# MCU.net
KiCad netlist of a schematic drawn in Altium Designer
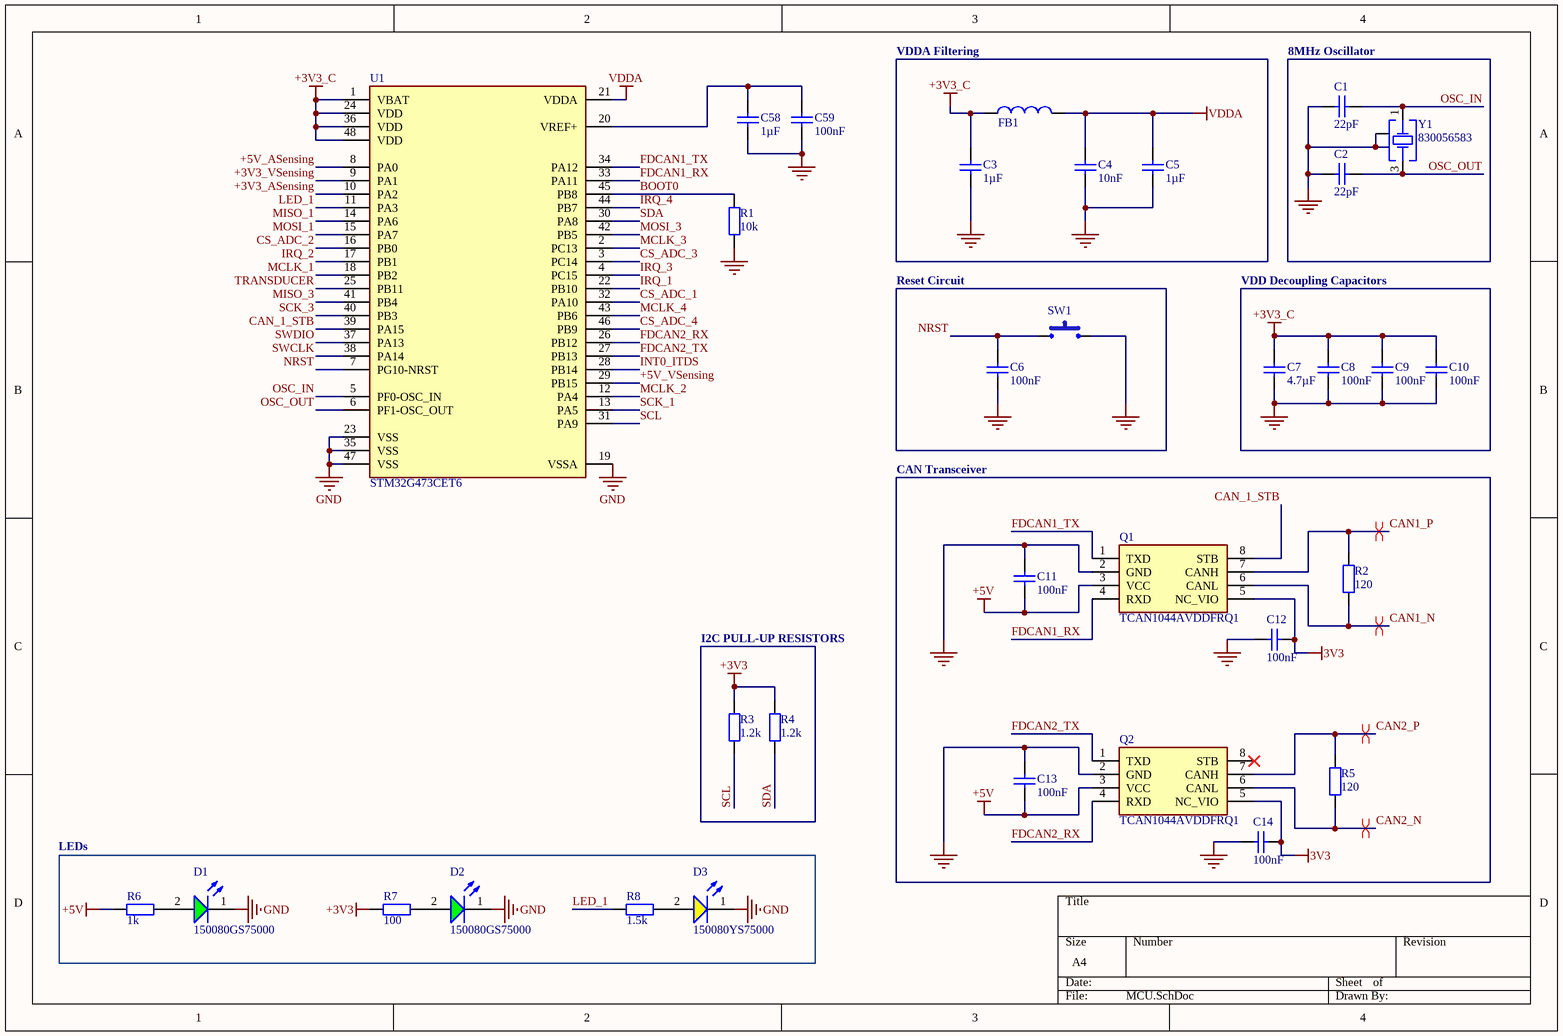
[diagram p0: MCU.SchDoc]

(export (version "E")
  (design (tool "Eeschema 10.0.6"))
  (components
    (comp (ref "C1")
      (value "22pF")
      (footprint "WCAP-CSGP_0603_L1.6W0.8H0.8_Reflow")
      (description "WCAP-CSGP Multilayer Ceramic Chip Capacitor, General Purpose, size 0603, NP0, 22pF, 25VDC")
      (fields
        (field (name "MANUFACTURER") "Wurth Elektronik")
        (field (name "MANUFACTURER PART NUMBER") "885012006034")
      )
      (libsource (lib "LEEM UPM") (part "885012209047R"))
    )
    (comp (ref "C2")
      (value "22pF")
      (footprint "WCAP-CSGP_0603_L1.6W0.8H0.8_Reflow")
      (description "WCAP-CSGP Multilayer Ceramic Chip Capacitor, General Purpose, size 0603, NP0, 22pF, 25VDC")
      (fields
        (field (name "MANUFACTURER") "Wurth Elektronik")
        (field (name "MANUFACTURER PART NUMBER") "885012006034")
      )
      (libsource (lib "LEEM UPM") (part "885012209047R"))
    )
    (comp (ref "C3")
      (value "1µF")
      (footprint "WCAP-CSGP_0603_L1.6W0.8H0.8_Reflow")
      (description "WCAP-CSGP Multilayer Ceramic Chip Capacitor, General Purpose, size 0603, X7R, 1uF, 16VDC")
      (fields
        (field (name "MANUFACTURER") "Wurth Elektronik")
        (field (name "MANUFACTURER PART NUMBER") "885012206052")
      )
      (libsource (lib "LEEM UPM") (part "885012209047R"))
    )
    (comp (ref "C4")
      (value "10nF")
      (footprint "WCAP-CSGP_0603_L1.6W0.8H0.8_Reflow")
      (description "WCAP-CSGP Multilayer Ceramic Chip Capacitor, General Purpose, size 0603, X7R, 10nF, 25VDC")
      (fields
        (field (name "MANUFACTURER") "Wurth Elektronik")
        (field (name "MANUFACTURER PART NUMBER") "885012206065")
      )
      (libsource (lib "LEEM UPM") (part "885012209047R"))
    )
    (comp (ref "C5")
      (value "1µF")
      (footprint "WCAP-CSGP_0603_L1.6W0.8H0.8_Reflow")
      (description "WCAP-CSGP Multilayer Ceramic Chip Capacitor, General Purpose, size 0603, X7R, 1uF, 16VDC")
      (fields
        (field (name "MANUFACTURER") "Wurth Elektronik")
        (field (name "MANUFACTURER PART NUMBER") "885012206052")
      )
      (libsource (lib "LEEM UPM") (part "885012209047R"))
    )
    (comp (ref "C6")
      (value "100nF")
      (footprint "WCAP-CSGP_0603_L1.6W0.8H0.8_Reflow")
      (description "WCAP-CSGP Multilayer Ceramic Chip Capacitor, General Purpose, size 0603, X7R, 100nF, 25VDC")
      (fields
        (field (name "MANUFACTURER") "Wurth Elektronik")
        (field (name "MANUFACTURER PART NUMBER") "885012206071")
      )
      (libsource (lib "LEEM UPM") (part "885012209047R"))
    )
    (comp (ref "C7")
      (value "4.7µF")
      (footprint "WCAP-CSGP_0603_L1.6W0.8H0.8_Reflow")
      (description "WCAP-CSGP Multilayer Ceramic Chip Capacitor, General Purpose, size 0603, X5R, 4.7uF, 10VDC")
      (fields
        (field (name "MANUFACTURER PART NUMBER") "885012106012")
        (field (name "MANUFACTURER") "Wurth Elektronik")
      )
      (libsource (lib "LEEM UPM") (part "885012209047R"))
    )
    (comp (ref "C8")
      (value "100nF")
      (footprint "WCAP-CSGP_0603_L1.6W0.8H0.8_Reflow")
      (description "WCAP-CSGP Multilayer Ceramic Chip Capacitor, General Purpose, size 0603, X7R, 100nF, 25VDC")
      (fields
        (field (name "MANUFACTURER") "Wurth Elektronik")
        (field (name "MANUFACTURER PART NUMBER") "885012206071")
      )
      (libsource (lib "LEEM UPM") (part "885012209047R"))
    )
    (comp (ref "C9")
      (value "100nF")
      (footprint "WCAP-CSGP_0603_L1.6W0.8H0.8_Reflow")
      (description "WCAP-CSGP Multilayer Ceramic Chip Capacitor, General Purpose, size 0603, X7R, 100nF, 25VDC")
      (fields
        (field (name "MANUFACTURER") "Wurth Elektronik")
        (field (name "MANUFACTURER PART NUMBER") "885012206071")
      )
      (libsource (lib "LEEM UPM") (part "885012209047R"))
    )
    (comp (ref "C10")
      (value "100nF")
      (footprint "WCAP-CSGP_0603_L1.6W0.8H0.8_Reflow")
      (description "WCAP-CSGP Multilayer Ceramic Chip Capacitor, General Purpose, size 0603, X7R, 100nF, 25VDC")
      (fields
        (field (name "MANUFACTURER") "Wurth Elektronik")
        (field (name "MANUFACTURER PART NUMBER") "885012206071")
      )
      (libsource (lib "LEEM UPM") (part "885012209047R"))
    )
    (comp (ref "C11")
      (value "100nF")
      (footprint "WCAP-CSGP_0603_L1.6W0.8H0.8_Reflow")
      (description "WCAP-CSGP Multilayer Ceramic Chip Capacitor, General Purpose, size 0603, X7R, 100nF, 25VDC")
      (fields
        (field (name "MANUFACTURER") "Wurth Elektronik")
        (field (name "MANUFACTURER PART NUMBER") "885012206071")
      )
      (libsource (lib "LEEM UPM") (part "885012209047R"))
    )
    (comp (ref "C12")
      (value "100nF")
      (footprint "WCAP-CSGP_0603_L1.6W0.8H0.8_Reflow")
      (description "WCAP-CSGP Multilayer Ceramic Chip Capacitor, General Purpose, size 0603, X7R, 100nF, 25VDC")
      (fields
        (field (name "MANUFACTURER") "Wurth Elektronik")
        (field (name "MANUFACTURER PART NUMBER") "885012206071")
      )
      (libsource (lib "LEEM UPM") (part "885012209047R"))
    )
    (comp (ref "C13")
      (value "100nF")
      (footprint "WCAP-CSGP_0603_L1.6W0.8H0.8_Reflow")
      (description "WCAP-CSGP Multilayer Ceramic Chip Capacitor, General Purpose, size 0603, X7R, 100nF, 25VDC")
      (fields
        (field (name "MANUFACTURER") "Wurth Elektronik")
        (field (name "MANUFACTURER PART NUMBER") "885012206071")
      )
      (libsource (lib "LEEM UPM") (part "885012209047R"))
    )
    (comp (ref "C14")
      (value "100nF")
      (footprint "WCAP-CSGP_0603_L1.6W0.8H0.8_Reflow")
      (description "WCAP-CSGP Multilayer Ceramic Chip Capacitor, General Purpose, size 0603, X7R, 100nF, 25VDC")
      (fields
        (field (name "MANUFACTURER") "Wurth Elektronik")
        (field (name "MANUFACTURER PART NUMBER") "885012206071")
      )
      (libsource (lib "LEEM UPM") (part "885012209047R"))
    )
    (comp (ref "C58")
      (value "1µF")
      (footprint "WCAP-CSGP_0603_L1.6W0.8H0.8_Reflow")
      (description "WCAP-CSGP Multilayer Ceramic Chip Capacitor, General Purpose, size 0603, X7R, 1uF, 16VDC")
      (fields
        (field (name "MANUFACTURER") "Wurth Elektronik")
        (field (name "MANUFACTURER PART NUMBER") "885012206052")
      )
      (libsource (lib "LEEM UPM") (part "885012209047R"))
    )
    (comp (ref "C59")
      (value "100nF")
      (footprint "WCAP-CSGP_0603_L1.6W0.8H0.8_Reflow")
      (description "WCAP-CSGP Multilayer Ceramic Chip Capacitor, General Purpose, size 0603, X7R, 100nF, 25VDC")
      (fields
        (field (name "MANUFACTURER") "Wurth Elektronik")
        (field (name "MANUFACTURER PART NUMBER") "885012206071")
      )
      (libsource (lib "LEEM UPM") (part "885012209047R"))
    )
    (comp (ref "D1")
      (value "150080GS75000")
      (footprint "WL-SMCW_0805_150080xx75000")
      (description "WL-SMCW Mono-color Chip LED Waterclear, SMT, size 0805, Green, 3.2V, 140°")
      (fields (field (name "MANUFACTURER") "Wurth Elektronik"))
      (libsource (lib "LEEM UPM") (part "150120VS87000"))
    )
    (comp (ref "D2")
      (value "150080GS75000")
      (footprint "WL-SMCW_0805_150080xx75000")
      (description "WL-SMCW Mono-color Chip LED Waterclear, SMT, size 0805, Green, 3.2V, 140°")
      (fields (field (name "MANUFACTURER") "Wurth Elektronik"))
      (libsource (lib "LEEM UPM") (part "150120VS87000"))
    )
    (comp (ref "D3")
      (value "150080YS75000")
      (footprint "WL-SMCW_0805_150080xx75000")
      (description "WL-SMCW Mono-color Chip LED Waterclear, SMT, size 0805, Yellow, 2V, 140°")
      (fields (field (name "MANUFACTURER") "Wurth Elektronik"))
      (libsource (lib "LEEM UPM") (part "150120YS87000"))
    )
    (comp (ref "FB1")
      (value "742792625")
      (footprint "WE-CBF_0603_L1.6W0.8H0.8_HC")
      (description "WE-CBF SMT EMI Suppression Ferrite Bead, size 0603, 120Ohm, 2A")
      (fields (field (name "MANUFACTURER") "Wurth Elektronik"))
      (libsource (lib "LEEM UPM") (part "7427928801"))
    )
    (comp (ref "Q1")
      (value "TCAN1044AVDDFRQ1")
      (footprint "FP-DDF0008A-MFG")
      (description "Enhanced automotive CAN transceiver with standby 8-SOT-23-THIN -40 to 150")
      (libsource (lib "LEEM UPM") (part "TCAN1044A"))
    )
    (comp (ref "Q2")
      (value "TCAN1044AVDDFRQ1")
      (footprint "FP-DDF0008A-MFG")
      (description "Enhanced automotive CAN transceiver with standby 8-SOT-23-THIN -40 to 150")
      (libsource (lib "LEEM UPM") (part "TCAN1044A"))
    )
    (comp (ref "R1")
      (value "10k")
      (footprint "WRIS-RSKS_0603_Reflow")
      (description "WRIS-RSKS Thick Film Resistor, size 0603, 10000Ohm, 100mW")
      (fields
        (field (name "MANUFACTURER") "Wurth Elektronik")
        (field (name "MANUFACTURER PART NUMBER") "560112116005")
      )
      (libsource (lib "LEEM UPM") (part "560112140010"))
    )
    (comp (ref "R2")
      (value "120")
      (footprint "RCS0805120RFKEA-Footprint-1")
      (fields (field (name "POWER") "500mW") (field (name "Comment") "RCS0805120RFKEA"))
      (libsource (lib "LEEM UPM") (part "RCS0805120"))
    )
    (comp (ref "R3")
      (value "1.2k")
      (footprint "WRIS-RSKS_0603_Reflow")
      (description "WRIS-RSKS Thick Film Resistor, size 0603, 1200Ohm, 100mW")
      (fields
        (field (name "MANUFACTURER PART NUMBER") "560112116070")
        (field (name "MANUFACTURER") "Wurth Elektronik")
      )
      (libsource (lib "LEEM UPM") (part "560112140010"))
    )
    (comp (ref "R4")
      (value "1.2k")
      (footprint "WRIS-RSKS_0603_Reflow")
      (description "WRIS-RSKS Thick Film Resistor, size 0603, 1200Ohm, 100mW")
      (fields
        (field (name "MANUFACTURER PART NUMBER") "560112116070")
        (field (name "MANUFACTURER") "Wurth Elektronik")
      )
      (libsource (lib "LEEM UPM") (part "560112140010"))
    )
    (comp (ref "R5")
      (value "120")
      (footprint "RCS0805120RFKEA-Footprint-1")
      (fields (field (name "POWER") "500mW") (field (name "Comment") "RCS0805120RFKEA"))
      (libsource (lib "LEEM UPM") (part "RCS0805120"))
    )
    (comp (ref "R6")
      (value "1k")
      (footprint "WRIS-RSKS_0603_Reflow")
      (description "WRIS-RSKS Thick Film Resistor, size 0603, 1000Ohm, 100mW")
      (fields
        (field (name "MANUFACTURER PART NUMBER") "560112116014")
        (field (name "MANUFACTURER") "Wurth Elektronik")
      )
      (libsource (lib "") (part "560112140010_1"))
    )
    (comp (ref "R7")
      (value "100")
      (footprint "WRIS-RSKS_0603_Reflow")
      (description "WRIS-RSKS Thick Film Resistor, size 0603, 100Ohm, 100mW")
      (fields
        (field (name "MANUFACTURER") "Wurth Elektronik")
        (field (name "MANUFACTURER PART NUMBER") "560112116009")
      )
      (libsource (lib "") (part "560112140010_1"))
    )
    (comp (ref "R8")
      (value "1.5k")
      (footprint "WRIS-RSKS_0603_Reflow")
      (description "WRIS-RSKS Thick Film Resistor, size 0603, 1500Ohm, 100mW")
      (fields
        (field (name "MANUFACTURER") "Wurth Elektronik")
        (field (name "MANUFACTURER PART NUMBER") "560112116038")
      )
      (libsource (lib "") (part "560112140010_1"))
    )
    (comp (ref "SW1")
      (value "PTS815SJM250SMTRLFS")
      (footprint "PTS815SJM250SMTRLFS-Footprint-1")
      (libsource (lib "LEEM UPM") (part "PTS815S"))
    )
    (comp (ref "U1")
      (value "STM32G473CET6")
      (footprint "STM32G0C1RET6-Footprint-1")
      (libsource (lib "LEEM UPM") (part "STM32G473xE"))
    )
    (comp (ref "Y1")
      (value "830056583")
      (footprint "WE-XTAL_CFPX-104")
      (description "WE-XTAL Quartz Crystal, SMT, CFPX-104, 10MHz, +/-30ppm")
      (fields (field (name "MANUFACTURER") "Wurth Elektronik"))
      (libsource (lib "LEEM UPM") (part "830108161901"))
    )
  )
  (nets
    (net (code "1") (name "+3V3") (class "Default")
      (node (ref "R3") (pin "2") (pinfunction "2_2") (pintype "passive"))
      (node (ref "R4") (pin "2") (pinfunction "2_2") (pintype "passive"))
      (node (ref "R7") (pin "1") (pinfunction "1_1") (pintype "passive"))
    )
    (net (code "2") (name "+3V3_C") (class "Default")
      (node (ref "C10") (pin "2") (pinfunction "2_2") (pintype "passive"))
      (node (ref "C12") (pin "1") (pinfunction "1_1") (pintype "passive"))
      (node (ref "C14") (pin "1") (pinfunction "1_1") (pintype "passive"))
      (node (ref "C3") (pin "2") (pinfunction "2_2") (pintype "passive"))
      (node (ref "C7") (pin "2") (pinfunction "2_2") (pintype "passive"))
      (node (ref "C8") (pin "2") (pinfunction "2_2") (pintype "passive"))
      (node (ref "C9") (pin "2") (pinfunction "2_2") (pintype "passive"))
      (node (ref "FB1") (pin "1") (pinfunction "1_1") (pintype "passive"))
      (node (ref "Q1") (pin "5") (pinfunction "NC_VIO_5") (pintype "passive"))
      (node (ref "Q2") (pin "5") (pinfunction "NC_VIO_5") (pintype "passive"))
      (node (ref "U1") (pin "1") (pinfunction "VBAT_1") (pintype "passive"))
      (node (ref "U1") (pin "24") (pinfunction "VDD_24") (pintype "passive"))
      (node (ref "U1") (pin "36") (pinfunction "VDD_36") (pintype "passive"))
      (node (ref "U1") (pin "48") (pinfunction "VDD_48") (pintype "passive"))
    )
    (net (code "3") (name "+5V") (class "Default")
      (node (ref "C11") (pin "1") (pinfunction "1_1") (pintype "passive"))
      (node (ref "C13") (pin "1") (pinfunction "1_1") (pintype "passive"))
      (node (ref "Q1") (pin "3") (pinfunction "VCC_3") (pintype "passive"))
      (node (ref "Q2") (pin "3") (pinfunction "VCC_3") (pintype "passive"))
      (node (ref "R6") (pin "1") (pinfunction "1_1") (pintype "passive"))
    )
    (net (code "4") (name "/+3V3_ASensing") (class "Default")
      (node (ref "U1") (pin "10") (pinfunction "PA2_10") (pintype "passive"))
    )
    (net (code "5") (name "/+3V3_VSensing") (class "Default")
      (node (ref "U1") (pin "9") (pinfunction "PA1_9") (pintype "passive"))
    )
    (net (code "6") (name "/+5V_ASensing") (class "Default")
      (node (ref "U1") (pin "8") (pinfunction "PA0_8") (pintype "passive"))
    )
    (net (code "7") (name "/+5V_VSensing") (class "Default")
      (node (ref "U1") (pin "29") (pinfunction "PB15_29") (pintype "passive"))
    )
    (net (code "8") (name "/BOOT0") (class "Default")
      (node (ref "R1") (pin "2") (pinfunction "2_2") (pintype "passive"))
      (node (ref "U1") (pin "45") (pinfunction "PB8_45") (pintype "passive"))
    )
    (net (code "9") (name "/CAN1_N") (class "Default")
      (node (ref "Q1") (pin "6") (pinfunction "CANL_6") (pintype "passive"))
      (node (ref "R2") (pin "1") (pinfunction "1_1") (pintype "passive"))
    )
    (net (code "10") (name "/CAN1_P") (class "Default")
      (node (ref "Q1") (pin "7") (pinfunction "CANH_7") (pintype "passive"))
      (node (ref "R2") (pin "2") (pinfunction "2_2") (pintype "passive"))
    )
    (net (code "11") (name "/CAN2_N") (class "Default")
      (node (ref "Q2") (pin "6") (pinfunction "CANL_6") (pintype "passive"))
      (node (ref "R5") (pin "1") (pinfunction "1_1") (pintype "passive"))
    )
    (net (code "12") (name "/CAN2_P") (class "Default")
      (node (ref "Q2") (pin "7") (pinfunction "CANH_7") (pintype "passive"))
      (node (ref "R5") (pin "2") (pinfunction "2_2") (pintype "passive"))
    )
    (net (code "13") (name "/CAN_1_STB") (class "Default")
      (node (ref "Q1") (pin "8") (pinfunction "STB_8") (pintype "passive"))
      (node (ref "U1") (pin "39") (pinfunction "PA15_39") (pintype "passive"))
    )
    (net (code "14") (name "/CS_ADC_1") (class "Default")
      (node (ref "U1") (pin "32") (pinfunction "PA10_32") (pintype "passive"))
    )
    (net (code "15") (name "/CS_ADC_2") (class "Default")
      (node (ref "U1") (pin "16") (pinfunction "PB0_16") (pintype "passive"))
    )
    (net (code "16") (name "/CS_ADC_3") (class "Default")
      (node (ref "U1") (pin "3") (pinfunction "PC14_3") (pintype "passive"))
    )
    (net (code "17") (name "/CS_ADC_4") (class "Default")
      (node (ref "U1") (pin "46") (pinfunction "PB9_46") (pintype "passive"))
    )
    (net (code "18") (name "/FDCAN1_RX") (class "Default")
      (node (ref "Q1") (pin "4") (pinfunction "RXD_4") (pintype "passive"))
      (node (ref "U1") (pin "33") (pinfunction "PA11_33") (pintype "passive"))
    )
    (net (code "19") (name "/FDCAN1_TX") (class "Default")
      (node (ref "Q1") (pin "1") (pinfunction "TXD_1") (pintype "passive"))
      (node (ref "U1") (pin "34") (pinfunction "PA12_34") (pintype "passive"))
    )
    (net (code "20") (name "/FDCAN2_RX") (class "Default")
      (node (ref "Q2") (pin "4") (pinfunction "RXD_4") (pintype "passive"))
      (node (ref "U1") (pin "26") (pinfunction "PB12_26") (pintype "passive"))
    )
    (net (code "21") (name "/FDCAN2_TX") (class "Default")
      (node (ref "Q2") (pin "1") (pinfunction "TXD_1") (pintype "passive"))
      (node (ref "U1") (pin "27") (pinfunction "PB13_27") (pintype "passive"))
    )
    (net (code "22") (name "/INT0_ITDS") (class "Default")
      (node (ref "U1") (pin "28") (pinfunction "PB14_28") (pintype "passive"))
    )
    (net (code "23") (name "/IRQ_1") (class "Default")
      (node (ref "U1") (pin "22") (pinfunction "PB10_22") (pintype "passive"))
    )
    (net (code "24") (name "/IRQ_2") (class "Default")
      (node (ref "U1") (pin "17") (pinfunction "PB1_17") (pintype "passive"))
    )
    (net (code "25") (name "/IRQ_3") (class "Default")
      (node (ref "U1") (pin "4") (pinfunction "PC15_4") (pintype "passive"))
    )
    (net (code "26") (name "/IRQ_4") (class "Default")
      (node (ref "U1") (pin "44") (pinfunction "PB7_44") (pintype "passive"))
    )
    (net (code "27") (name "/LED_1") (class "Default")
      (node (ref "R8") (pin "1") (pinfunction "1_1") (pintype "passive"))
      (node (ref "U1") (pin "11") (pinfunction "PA3_11") (pintype "passive"))
    )
    (net (code "28") (name "/MCLK_1") (class "Default")
      (node (ref "U1") (pin "18") (pinfunction "PB2_18") (pintype "passive"))
    )
    (net (code "29") (name "/MCLK_2") (class "Default")
      (node (ref "U1") (pin "12") (pinfunction "PA4_12") (pintype "passive"))
    )
    (net (code "30") (name "/MCLK_3") (class "Default")
      (node (ref "U1") (pin "2") (pinfunction "PC13_2") (pintype "passive"))
    )
    (net (code "31") (name "/MCLK_4") (class "Default")
      (node (ref "U1") (pin "43") (pinfunction "PB6_43") (pintype "passive"))
    )
    (net (code "32") (name "/MISO_1") (class "Default")
      (node (ref "U1") (pin "14") (pinfunction "PA6_14") (pintype "passive"))
    )
    (net (code "33") (name "/MISO_3") (class "Default")
      (node (ref "U1") (pin "41") (pinfunction "PB4_41") (pintype "passive"))
    )
    (net (code "34") (name "/MOSI_1") (class "Default")
      (node (ref "U1") (pin "15") (pinfunction "PA7_15") (pintype "passive"))
    )
    (net (code "35") (name "/MOSI_3") (class "Default")
      (node (ref "U1") (pin "42") (pinfunction "PB5_42") (pintype "passive"))
    )
    (net (code "36") (name "/NRST") (class "Default")
      (node (ref "C6") (pin "2") (pinfunction "2_2") (pintype "passive"))
      (node (ref "SW1") (pin "1") (pinfunction "1_1") (pintype "passive"))
      (node (ref "U1") (pin "7") (pinfunction "PG10-NRST_7") (pintype "passive"))
    )
    (net (code "37") (name "/OSC_IN") (class "Default")
      (node (ref "C1") (pin "1") (pinfunction "1_1") (pintype "passive"))
      (node (ref "U1") (pin "5") (pinfunction "PF0-OSC_IN_5") (pintype "passive"))
      (node (ref "Y1") (pin "1") (pinfunction "Crystal_1") (pintype "passive"))
    )
    (net (code "38") (name "/OSC_OUT") (class "Default")
      (node (ref "C2") (pin "1") (pinfunction "1_1") (pintype "passive"))
      (node (ref "U1") (pin "6") (pinfunction "PF1-OSC_OUT_6") (pintype "passive"))
      (node (ref "Y1") (pin "3") (pinfunction "Crystal_3") (pintype "passive"))
    )
    (net (code "39") (name "/SCK_1") (class "Default")
      (node (ref "U1") (pin "13") (pinfunction "PA5_13") (pintype "passive"))
    )
    (net (code "40") (name "/SCK_3") (class "Default")
      (node (ref "U1") (pin "40") (pinfunction "PB3_40") (pintype "passive"))
    )
    (net (code "41") (name "/SCL") (class "Default")
      (node (ref "R3") (pin "1") (pinfunction "1_1") (pintype "passive"))
      (node (ref "U1") (pin "31") (pinfunction "PA9_31") (pintype "passive"))
    )
    (net (code "42") (name "/SDA") (class "Default")
      (node (ref "R4") (pin "1") (pinfunction "1_1") (pintype "passive"))
      (node (ref "U1") (pin "30") (pinfunction "PA8_30") (pintype "passive"))
    )
    (net (code "43") (name "/SWCLK") (class "Default")
      (node (ref "U1") (pin "38") (pinfunction "PA14_38") (pintype "passive"))
    )
    (net (code "44") (name "/SWDIO") (class "Default")
      (node (ref "U1") (pin "37") (pinfunction "PA13_37") (pintype "passive"))
    )
    (net (code "45") (name "/TRANSDUCER") (class "Default")
      (node (ref "U1") (pin "25") (pinfunction "PB11_25") (pintype "passive"))
    )
    (net (code "46") (name "GND") (class "Default")
      (node (ref "C1") (pin "2") (pinfunction "2_2") (pintype "passive"))
      (node (ref "C10") (pin "1") (pinfunction "1_1") (pintype "passive"))
      (node (ref "C11") (pin "2") (pinfunction "2_2") (pintype "passive"))
      (node (ref "C12") (pin "2") (pinfunction "2_2") (pintype "passive"))
      (node (ref "C13") (pin "2") (pinfunction "2_2") (pintype "passive"))
      (node (ref "C14") (pin "2") (pinfunction "2_2") (pintype "passive"))
      (node (ref "C2") (pin "2") (pinfunction "2_2") (pintype "passive"))
      (node (ref "C3") (pin "1") (pinfunction "1_1") (pintype "passive"))
      (node (ref "C4") (pin "1") (pinfunction "1_1") (pintype "passive"))
      (node (ref "C5") (pin "1") (pinfunction "1_1") (pintype "passive"))
      (node (ref "C58") (pin "1") (pinfunction "1_1") (pintype "passive"))
      (node (ref "C59") (pin "1") (pinfunction "1_1") (pintype "passive"))
      (node (ref "C6") (pin "1") (pinfunction "1_1") (pintype "passive"))
      (node (ref "C7") (pin "1") (pinfunction "1_1") (pintype "passive"))
      (node (ref "C8") (pin "1") (pinfunction "1_1") (pintype "passive"))
      (node (ref "C9") (pin "1") (pinfunction "1_1") (pintype "passive"))
      (node (ref "D1") (pin "1") (pinfunction "K_1") (pintype "passive"))
      (node (ref "D2") (pin "1") (pinfunction "K_1") (pintype "passive"))
      (node (ref "D3") (pin "1") (pinfunction "K_1") (pintype "passive"))
      (node (ref "Q1") (pin "2") (pinfunction "GND_2") (pintype "passive"))
      (node (ref "Q2") (pin "2") (pinfunction "GND_2") (pintype "passive"))
      (node (ref "R1") (pin "1") (pinfunction "1_1") (pintype "passive"))
      (node (ref "SW1") (pin "2") (pinfunction "2_2") (pintype "passive"))
      (node (ref "U1") (pin "19") (pinfunction "VSSA_19") (pintype "passive"))
      (node (ref "U1") (pin "23") (pinfunction "VSS_23") (pintype "passive"))
      (node (ref "U1") (pin "35") (pinfunction "VSS_35") (pintype "passive"))
      (node (ref "U1") (pin "47") (pinfunction "VSS_47") (pintype "passive"))
      (node (ref "Y1") (pin "2") (pinfunction "GND_&_Lid_2") (pintype "passive"))
      (node (ref "Y1") (pin "4") (pinfunction "GND_&_Lid_4") (pintype "passive"))
    )
    (net (code "47") (name "Net-(D1-A)") (class "Default")
      (node (ref "D1") (pin "2") (pinfunction "A_2") (pintype "passive"))
      (node (ref "R6") (pin "2") (pinfunction "2_2") (pintype "passive"))
    )
    (net (code "48") (name "Net-(D2-A)") (class "Default")
      (node (ref "D2") (pin "2") (pinfunction "A_2") (pintype "passive"))
      (node (ref "R7") (pin "2") (pinfunction "2_2") (pintype "passive"))
    )
    (net (code "49") (name "Net-(D3-A)") (class "Default")
      (node (ref "D3") (pin "2") (pinfunction "A_2") (pintype "passive"))
      (node (ref "R8") (pin "2") (pinfunction "2_2") (pintype "passive"))
    )
    (net (code "50") (name "Net-(U1-VREF+)") (class "Default")
      (node (ref "C58") (pin "2") (pinfunction "2_2") (pintype "passive"))
      (node (ref "C59") (pin "2") (pinfunction "2_2") (pintype "passive"))
      (node (ref "U1") (pin "20") (pinfunction "VREF+_20") (pintype "passive"))
    )
    (net (code "51") (name "VDDA") (class "Default")
      (node (ref "C4") (pin "2") (pinfunction "2_2") (pintype "passive"))
      (node (ref "C5") (pin "2") (pinfunction "2_2") (pintype "passive"))
      (node (ref "FB1") (pin "2") (pinfunction "2_2") (pintype "passive"))
      (node (ref "U1") (pin "21") (pinfunction "VDDA_21") (pintype "passive"))
    )
    (net (code "52") (name "unconnected-(Q2-STB-Pad8)") (class "Default")
      (node (ref "Q2") (pin "8") (pinfunction "STB_8") (pintype "passive+no_connect"))
    )
  )
)
